# Schematic.net
KiCad netlist of a schematic drawn in EAGLE
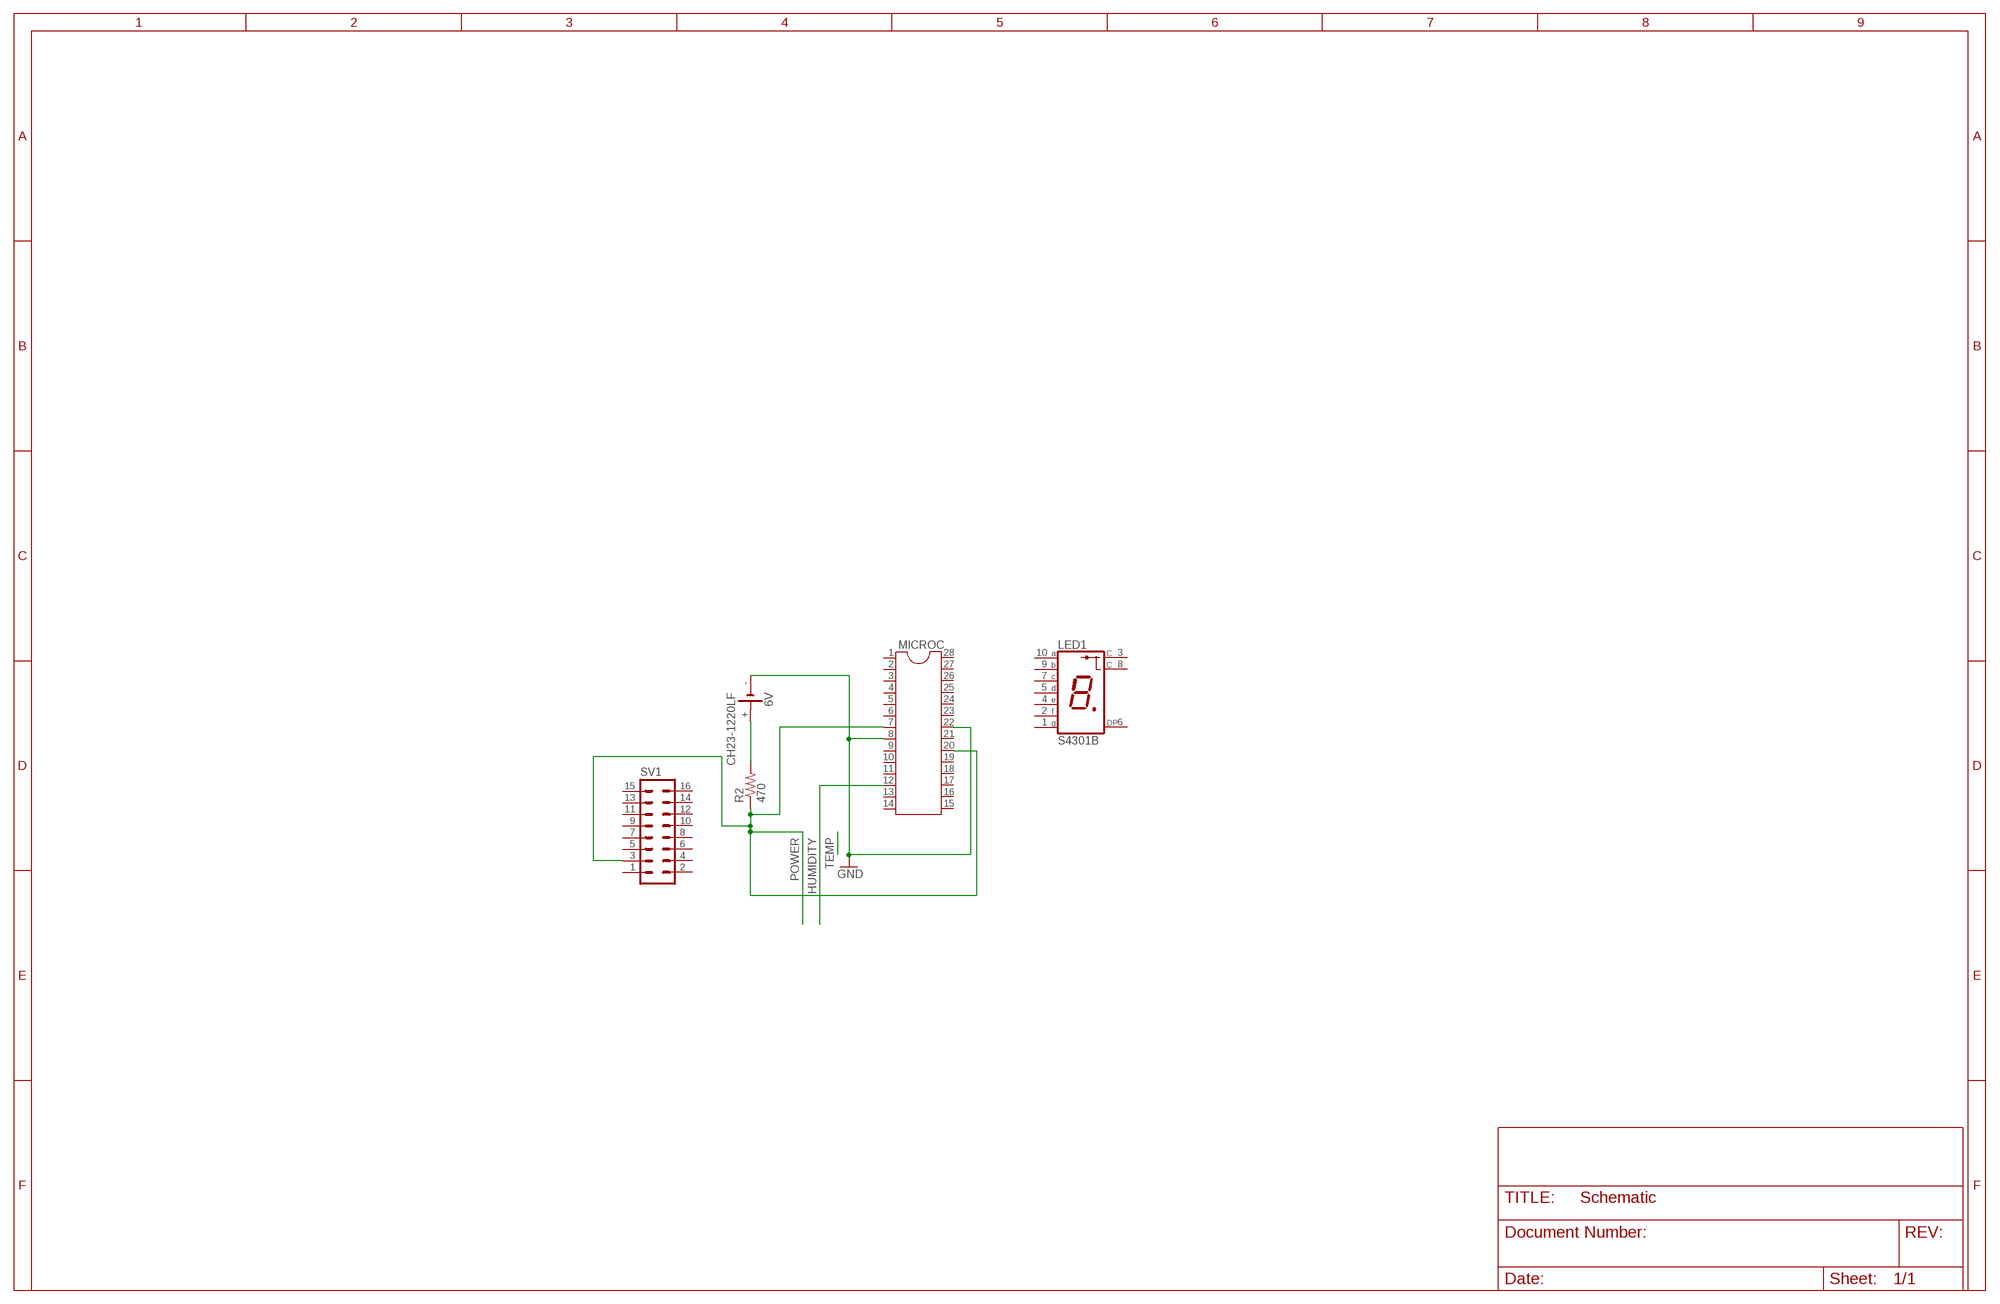
[diagram p0: schematic, sheet 1]

(export (version "E")
  (design (tool "Eeschema 10.0.6"))
  (components
    (comp (ref "6V")
      (value "CH23-1220LF")
      (footprint "eagle-import:CH23-1220LF")
      (libsource (lib "eagle-import") (part "CH23-1220LF"))
    )
    (comp (ref "LED1")
      (value "S4301B")
      (footprint "eagle-import:S4301B")
      (libsource (lib "eagle-import") (part "S4301B"))
    )
    (comp (ref "MICROC")
      (value "DIL28")
      (footprint "eagle-import:DIL28-6")
      (libsource (lib "eagle-import") (part "DIL28"))
    )
    (comp (ref "R2")
      (value "470")
      (footprint "eagle-import:0204V")
      (libsource (lib "eagle-import") (part "R-US_0204/2V"))
    )
    (comp (ref "SV1")
      (value "16PL")
      (footprint "eagle-import:16PL")
      (libsource (lib "eagle-import") (part "16PL"))
    )
  )
  (nets
    (net (code "1") (name "/HUMIDITY") (class "Default")
      (node (ref "MICROC") (pin "12") (pinfunction "12_12") (pintype "passive"))
    )
    (net (code "2") (name "/POWER") (class "Default")
      (node (ref "MICROC") (pin "20") (pinfunction "20_20") (pintype "passive"))
      (node (ref "MICROC") (pin "7") (pinfunction "7_7") (pintype "passive"))
      (node (ref "R2") (pin "1") (pinfunction "1_1") (pintype "passive"))
      (node (ref "SV1") (pin "3") (pinfunction "3_3") (pintype "passive"))
    )
    (net (code "4") (name "GND") (class "Default")
      (node (ref "6V") (pin "-") (pinfunction "-_-") (pintype "passive"))
      (node (ref "MICROC") (pin "22") (pinfunction "22_22") (pintype "passive"))
      (node (ref "MICROC") (pin "8") (pinfunction "8_8") (pintype "passive"))
    )
    (net (code "5") (name "Net-(6V-Pad+)") (class "Default")
      (node (ref "6V") (pin "+") (pinfunction "+_+") (pintype "passive"))
      (node (ref "R2") (pin "2") (pinfunction "2_2") (pintype "passive"))
    )
    (net (code "6") (name "unconnected-(LED1-A-Pad10)") (class "Default")
      (node (ref "LED1") (pin "10") (pinfunction "A_10") (pintype "passive"))
    )
    (net (code "7") (name "unconnected-(LED1-B-Pad9)") (class "Default")
      (node (ref "LED1") (pin "9") (pinfunction "B_9") (pintype "passive"))
    )
    (net (code "8") (name "unconnected-(LED1-C-Pad3)") (class "Default")
      (node (ref "LED1") (pin "3") (pinfunction "C_3") (pintype "passive"))
    )
    (net (code "9") (name "unconnected-(LED1-C-Pad7)") (class "Default")
      (node (ref "LED1") (pin "7") (pinfunction "C_7") (pintype "passive"))
    )
    (net (code "10") (name "unconnected-(LED1-C-Pad8)") (class "Default")
      (node (ref "LED1") (pin "8") (pinfunction "C_8") (pintype "passive"))
    )
    (net (code "11") (name "unconnected-(LED1-D-Pad5)") (class "Default")
      (node (ref "LED1") (pin "5") (pinfunction "D_5") (pintype "passive"))
    )
    (net (code "12") (name "unconnected-(LED1-DP-Pad6)") (class "Default")
      (node (ref "LED1") (pin "6") (pinfunction "DP_6") (pintype "passive"))
    )
    (net (code "13") (name "unconnected-(LED1-E-Pad4)") (class "Default")
      (node (ref "LED1") (pin "4") (pinfunction "E_4") (pintype "passive"))
    )
    (net (code "14") (name "unconnected-(LED1-F-Pad2)") (class "Default")
      (node (ref "LED1") (pin "2") (pinfunction "F_2") (pintype "passive"))
    )
    (net (code "15") (name "unconnected-(LED1-G-Pad1)") (class "Default")
      (node (ref "LED1") (pin "1") (pinfunction "G_1") (pintype "passive"))
    )
    (net (code "16") (name "unconnected-(MICROC-Pad1)") (class "Default")
      (node (ref "MICROC") (pin "1") (pinfunction "1_1") (pintype "passive"))
    )
    (net (code "17") (name "unconnected-(MICROC-Pad2)") (class "Default")
      (node (ref "MICROC") (pin "2") (pinfunction "2_2") (pintype "passive"))
    )
    (net (code "18") (name "unconnected-(MICROC-Pad3)") (class "Default")
      (node (ref "MICROC") (pin "3") (pinfunction "3_3") (pintype "passive"))
    )
    (net (code "19") (name "unconnected-(MICROC-Pad4)") (class "Default")
      (node (ref "MICROC") (pin "4") (pinfunction "4_4") (pintype "passive"))
    )
    (net (code "20") (name "unconnected-(MICROC-Pad5)") (class "Default")
      (node (ref "MICROC") (pin "5") (pinfunction "5_5") (pintype "passive"))
    )
    (net (code "21") (name "unconnected-(MICROC-Pad6)") (class "Default")
      (node (ref "MICROC") (pin "6") (pinfunction "6_6") (pintype "passive"))
    )
    (net (code "22") (name "unconnected-(MICROC-Pad9)") (class "Default")
      (node (ref "MICROC") (pin "9") (pinfunction "9_9") (pintype "passive"))
    )
    (net (code "23") (name "unconnected-(MICROC-Pad10)") (class "Default")
      (node (ref "MICROC") (pin "10") (pinfunction "10_10") (pintype "passive"))
    )
    (net (code "24") (name "unconnected-(MICROC-Pad11)") (class "Default")
      (node (ref "MICROC") (pin "11") (pinfunction "11_11") (pintype "passive"))
    )
    (net (code "25") (name "unconnected-(MICROC-Pad13)") (class "Default")
      (node (ref "MICROC") (pin "13") (pinfunction "13_13") (pintype "passive"))
    )
    (net (code "26") (name "unconnected-(MICROC-Pad14)") (class "Default")
      (node (ref "MICROC") (pin "14") (pinfunction "14_14") (pintype "passive"))
    )
    (net (code "27") (name "unconnected-(MICROC-Pad15)") (class "Default")
      (node (ref "MICROC") (pin "15") (pinfunction "15_15") (pintype "passive"))
    )
    (net (code "28") (name "unconnected-(MICROC-Pad16)") (class "Default")
      (node (ref "MICROC") (pin "16") (pinfunction "16_16") (pintype "passive"))
    )
    (net (code "29") (name "unconnected-(MICROC-Pad17)") (class "Default")
      (node (ref "MICROC") (pin "17") (pinfunction "17_17") (pintype "passive"))
    )
    (net (code "30") (name "unconnected-(MICROC-Pad18)") (class "Default")
      (node (ref "MICROC") (pin "18") (pinfunction "18_18") (pintype "passive"))
    )
    (net (code "31") (name "unconnected-(MICROC-Pad19)") (class "Default")
      (node (ref "MICROC") (pin "19") (pinfunction "19_19") (pintype "passive"))
    )
    (net (code "32") (name "unconnected-(MICROC-Pad21)") (class "Default")
      (node (ref "MICROC") (pin "21") (pinfunction "21_21") (pintype "passive"))
    )
    (net (code "33") (name "unconnected-(MICROC-Pad23)") (class "Default")
      (node (ref "MICROC") (pin "23") (pinfunction "23_23") (pintype "passive"))
    )
    (net (code "34") (name "unconnected-(MICROC-Pad24)") (class "Default")
      (node (ref "MICROC") (pin "24") (pinfunction "24_24") (pintype "passive"))
    )
    (net (code "35") (name "unconnected-(MICROC-Pad25)") (class "Default")
      (node (ref "MICROC") (pin "25") (pinfunction "25_25") (pintype "passive"))
    )
    (net (code "36") (name "unconnected-(MICROC-Pad26)") (class "Default")
      (node (ref "MICROC") (pin "26") (pinfunction "26_26") (pintype "passive"))
    )
    (net (code "37") (name "unconnected-(MICROC-Pad27)") (class "Default")
      (node (ref "MICROC") (pin "27") (pinfunction "27_27") (pintype "passive"))
    )
    (net (code "38") (name "unconnected-(MICROC-Pad28)") (class "Default")
      (node (ref "MICROC") (pin "28") (pinfunction "28_28") (pintype "passive"))
    )
    (net (code "39") (name "unconnected-(SV1-Pad1)") (class "Default")
      (node (ref "SV1") (pin "1") (pinfunction "1_1") (pintype "passive"))
    )
    (net (code "40") (name "unconnected-(SV1-Pad2)") (class "Default")
      (node (ref "SV1") (pin "2") (pinfunction "2_2") (pintype "passive"))
    )
    (net (code "41") (name "unconnected-(SV1-Pad4)") (class "Default")
      (node (ref "SV1") (pin "4") (pinfunction "4_4") (pintype "passive"))
    )
    (net (code "42") (name "unconnected-(SV1-Pad5)") (class "Default")
      (node (ref "SV1") (pin "5") (pinfunction "5_5") (pintype "passive"))
    )
    (net (code "43") (name "unconnected-(SV1-Pad6)") (class "Default")
      (node (ref "SV1") (pin "6") (pinfunction "6_6") (pintype "passive"))
    )
    (net (code "44") (name "unconnected-(SV1-Pad7)") (class "Default")
      (node (ref "SV1") (pin "7") (pinfunction "7_7") (pintype "passive"))
    )
    (net (code "45") (name "unconnected-(SV1-Pad8)") (class "Default")
      (node (ref "SV1") (pin "8") (pinfunction "8_8") (pintype "passive"))
    )
    (net (code "46") (name "unconnected-(SV1-Pad9)") (class "Default")
      (node (ref "SV1") (pin "9") (pinfunction "9_9") (pintype "passive"))
    )
    (net (code "47") (name "unconnected-(SV1-Pad10)") (class "Default")
      (node (ref "SV1") (pin "10") (pinfunction "10_10") (pintype "passive"))
    )
    (net (code "48") (name "unconnected-(SV1-Pad11)") (class "Default")
      (node (ref "SV1") (pin "11") (pinfunction "11_11") (pintype "passive"))
    )
    (net (code "49") (name "unconnected-(SV1-Pad12)") (class "Default")
      (node (ref "SV1") (pin "12") (pinfunction "12_12") (pintype "passive"))
    )
    (net (code "50") (name "unconnected-(SV1-Pad13)") (class "Default")
      (node (ref "SV1") (pin "13") (pinfunction "13_13") (pintype "passive"))
    )
    (net (code "51") (name "unconnected-(SV1-Pad14)") (class "Default")
      (node (ref "SV1") (pin "14") (pinfunction "14_14") (pintype "passive"))
    )
    (net (code "52") (name "unconnected-(SV1-Pad15)") (class "Default")
      (node (ref "SV1") (pin "15") (pinfunction "15_15") (pintype "passive"))
    )
    (net (code "53") (name "unconnected-(SV1-Pad16)") (class "Default")
      (node (ref "SV1") (pin "16") (pinfunction "16_16") (pintype "passive"))
    )
  )
)
